# WiFi_Block_Controller_v3.net
KiCad netlist of a schematic drawn in EAGLE
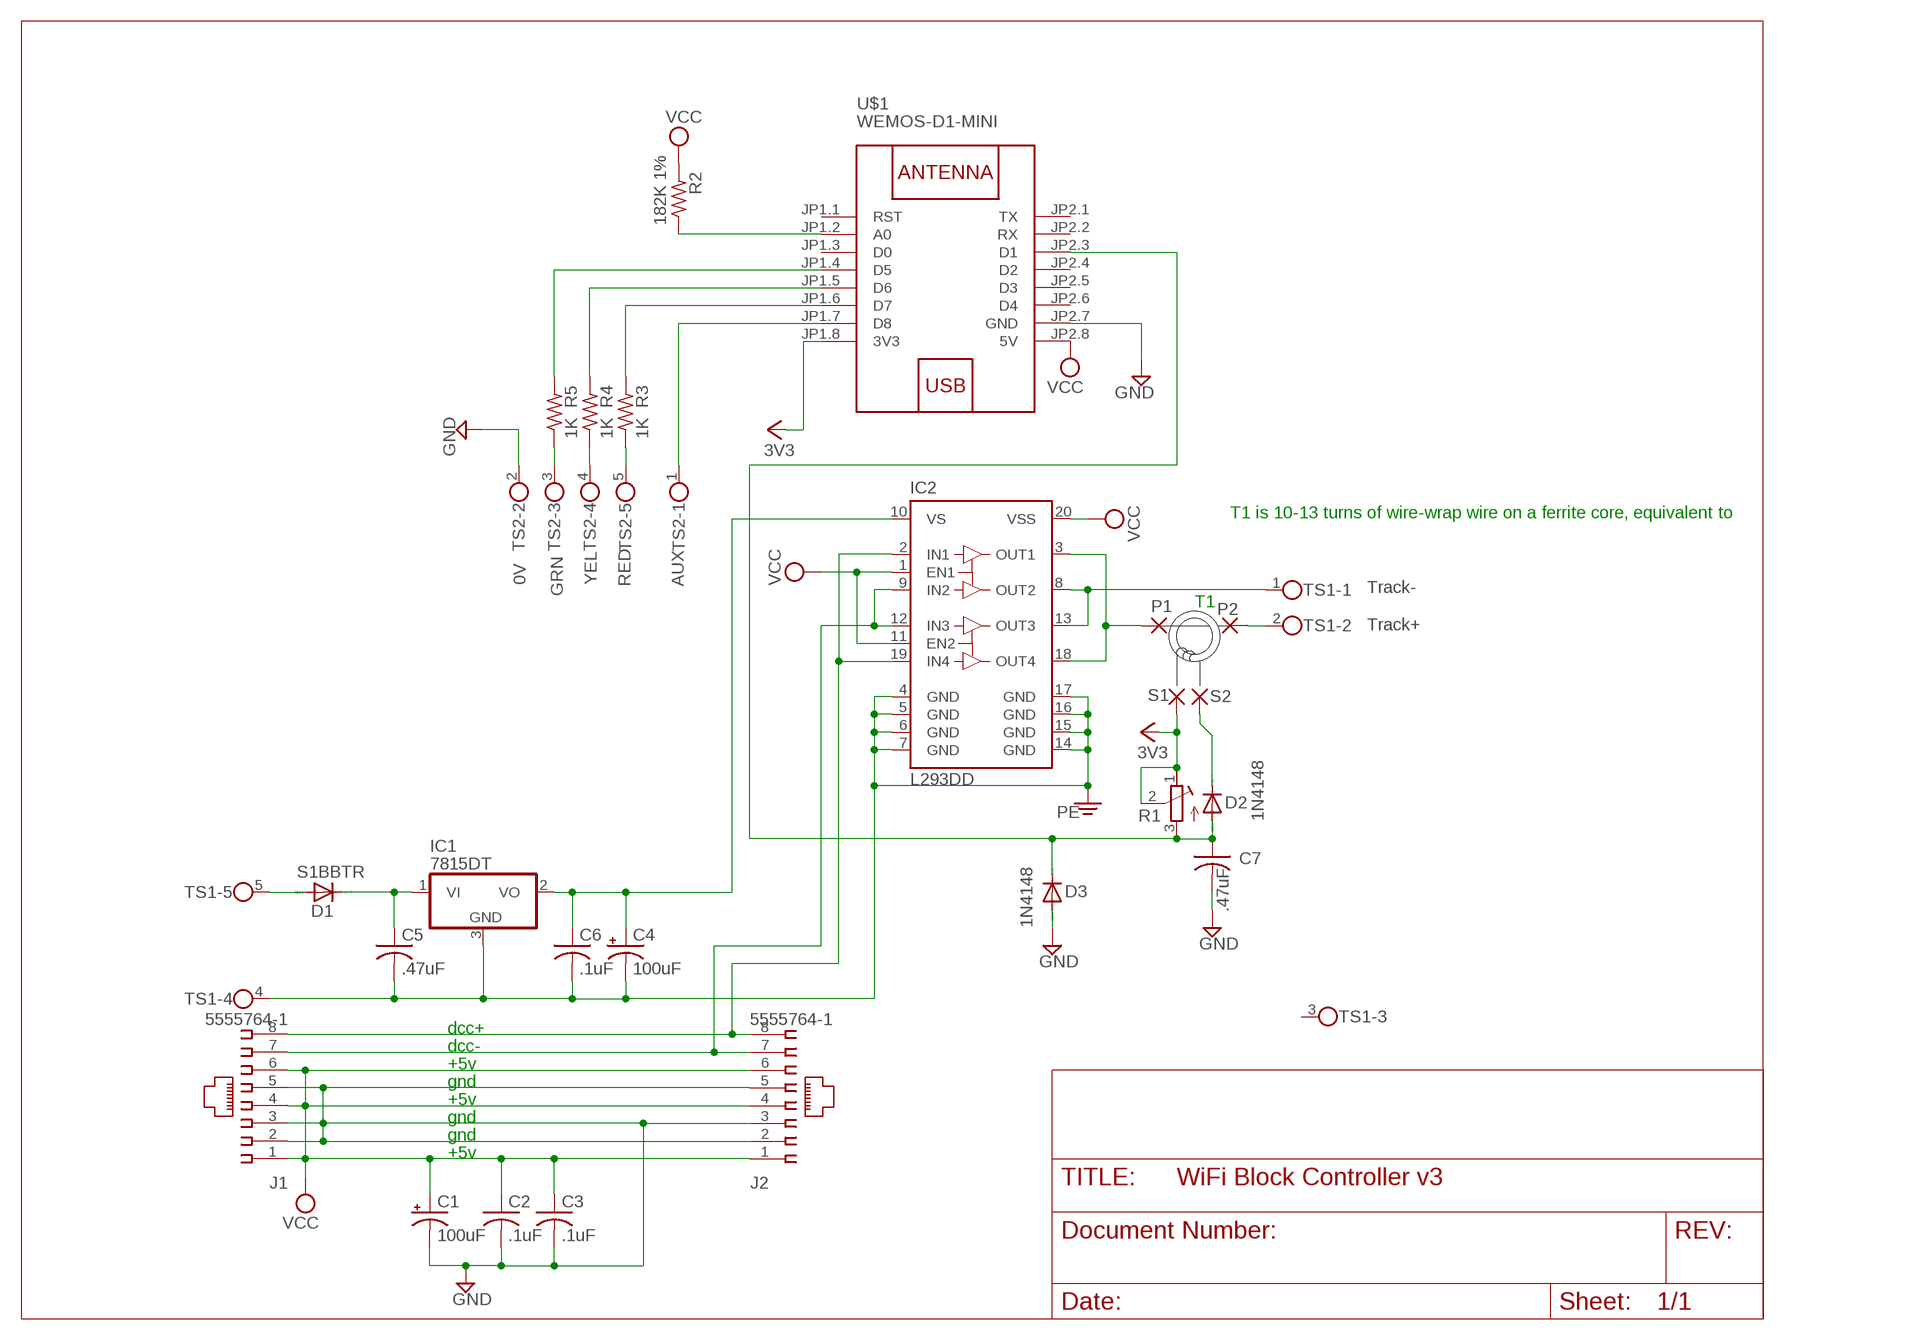
[diagram p0: schematic, sheet 1]

(export (version "E")
  (design (tool "Eeschema 10.0.6"))
  (components
    (comp (ref "C1")
      (value "100uF")
      (footprint "eagle-import:E3,5-8")
      (libsource (lib "eagle-import") (part "CPOL-USE3.5-8"))
    )
    (comp (ref "C2")
      (value ".1uF")
      (footprint "eagle-import:C1206")
      (libsource (lib "eagle-import") (part "C-USC1206"))
    )
    (comp (ref "C3")
      (value ".1uF")
      (footprint "eagle-import:C1206")
      (libsource (lib "eagle-import") (part "C-USC1206"))
    )
    (comp (ref "C4")
      (value "100uF")
      (footprint "eagle-import:E3,5-8")
      (libsource (lib "eagle-import") (part "CPOL-USE3.5-8"))
    )
    (comp (ref "C5")
      (value ".47uF")
      (footprint "eagle-import:C1206")
      (libsource (lib "eagle-import") (part "C-USC1206"))
    )
    (comp (ref "C6")
      (value ".1uF")
      (footprint "eagle-import:C1206")
      (libsource (lib "eagle-import") (part "C-USC1206"))
    )
    (comp (ref "C7")
      (value ".47uF")
      (footprint "eagle-import:C1206")
      (libsource (lib "eagle-import") (part "C-USC1206"))
    )
    (comp (ref "D1")
      (value "S1BBTR")
      (footprint "eagle-import:DO-214AC")
      (libsource (lib "eagle-import") (part "DIODE-DO-214AC"))
    )
    (comp (ref "D2")
      (value "1N4148")
      (footprint "eagle-import:SOD123")
      (libsource (lib "eagle-import") (part "DIODE-SOD123"))
    )
    (comp (ref "D3")
      (value "1N4148")
      (footprint "eagle-import:SOD123")
      (libsource (lib "eagle-import") (part "DIODE-SOD123"))
    )
    (comp (ref "IC1")
      (value "7815DT")
      (footprint "eagle-import:TO252")
      (libsource (lib "eagle-import") (part "78DT18"))
    )
    (comp (ref "IC2")
      (value "L293DD")
      (footprint "eagle-import:SO20")
      (libsource (lib "eagle-import") (part "L293DD"))
    )
    (comp (ref "J1")
      (value "5555764-1")
      (footprint "eagle-import:520426-4")
      (libsource (lib "eagle-import") (part "520426-4"))
    )
    (comp (ref "J2")
      (value "5555764-1")
      (footprint "eagle-import:520426-4")
      (libsource (lib "eagle-import") (part "520426-4"))
    )
    (comp (ref "P1")
      (value "NA")
      (footprint "eagle-import:2,15_1,0")
      (libsource (lib "eagle-import") (part "2,15/1,0"))
    )
    (comp (ref "P2")
      (value "NA")
      (footprint "eagle-import:2,15_1,0")
      (libsource (lib "eagle-import") (part "2,15/1,0"))
    )
    (comp (ref "R1")
      (value "R-TRIMM3314G")
      (footprint "eagle-import:RTRIM3314G")
      (libsource (lib "eagle-import") (part "R-TRIMM3314G"))
    )
    (comp (ref "R2")
      (value "182K 1%")
      (footprint "eagle-import:M1206")
      (libsource (lib "eagle-import") (part "R-US_M1206"))
    )
    (comp (ref "R3")
      (value "1K")
      (footprint "eagle-import:M1206")
      (libsource (lib "eagle-import") (part "R-US_M1206"))
    )
    (comp (ref "R4")
      (value "1K")
      (footprint "eagle-import:M1206")
      (libsource (lib "eagle-import") (part "R-US_M1206"))
    )
    (comp (ref "R5")
      (value "1K")
      (footprint "eagle-import:M1206")
      (libsource (lib "eagle-import") (part "R-US_M1206"))
    )
    (comp (ref "S1")
      (value "2,15/1,0")
      (footprint "eagle-import:2,15_1,0")
      (libsource (lib "eagle-import") (part "2,15/1,0"))
    )
    (comp (ref "S2")
      (value "2,15/1,0")
      (footprint "eagle-import:2,15_1,0")
      (libsource (lib "eagle-import") (part "2,15/1,0"))
    )
    (comp (ref "TS1")
      (value "TERMBLK05")
      (footprint "eagle-import:05PB")
      (libsource (lib "eagle-import") (part "TERMBLK05"))
    )
    (comp (ref "TS2")
      (value "TERMBLK05")
      (footprint "eagle-import:05PB")
      (libsource (lib "eagle-import") (part "TERMBLK05"))
    )
    (comp (ref "U$1")
      (value "WEMOS-D1-MINI")
      (footprint "eagle-import:WEMOS-D1-MINI")
      (libsource (lib "eagle-import") (part "WEMOS-D1-MINI"))
    )
  )
  (nets
    (net (code "1") (name "3V3") (class "Default")
      (node (ref "R1") (pin "1") (pinfunction "E_1") (pintype "passive"))
      (node (ref "R1") (pin "2") (pinfunction "S_2") (pintype "passive"))
      (node (ref "S1") (pin "1") (pinfunction "P_1") (pintype "passive"))
      (node (ref "U$1") (pin "JP1.8") (pinfunction "3V3_JP1.8") (pintype "power_in"))
    )
    (net (code "2") (name "GND") (class "Default")
      (node (ref "C1") (pin "-") (pinfunction "-_-") (pintype "passive"))
      (node (ref "C2") (pin "2") (pinfunction "2_2") (pintype "passive"))
      (node (ref "C3") (pin "2") (pinfunction "2_2") (pintype "passive"))
      (node (ref "C7") (pin "2") (pinfunction "2_2") (pintype "passive"))
      (node (ref "D3") (pin "A") (pinfunction "A_A") (pintype "passive"))
      (node (ref "J1") (pin "2") (pinfunction "2_2") (pintype "passive"))
      (node (ref "J1") (pin "3") (pinfunction "3_3") (pintype "passive"))
      (node (ref "J1") (pin "5") (pinfunction "5_5") (pintype "passive"))
      (node (ref "J2") (pin "2") (pinfunction "2_2") (pintype "passive"))
      (node (ref "J2") (pin "3") (pinfunction "3_3") (pintype "passive"))
      (node (ref "J2") (pin "5") (pinfunction "5_5") (pintype "passive"))
      (node (ref "TS2") (pin "2") (pinfunction "1_2") (pintype "passive"))
      (node (ref "U$1") (pin "JP2.7") (pinfunction "GND_JP2.7") (pintype "power_in"))
    )
    (net (code "3") (name "Net-(IC1-VI)") (class "Default")
      (node (ref "C5") (pin "1") (pinfunction "1_1") (pintype "passive"))
      (node (ref "D1") (pin "C") (pinfunction "C_C") (pintype "passive"))
      (node (ref "IC1") (pin "1") (pinfunction "VI_1") (pintype "input"))
    )
    (net (code "4") (name "Net-(IC1-VO)") (class "Default")
      (node (ref "C4") (pin "+") (pinfunction "+_+") (pintype "passive"))
      (node (ref "C6") (pin "1") (pinfunction "1_1") (pintype "passive"))
      (node (ref "IC1") (pin "2") (pinfunction "VO_2") (pintype "passive"))
      (node (ref "IC2") (pin "10") (pinfunction "VS_10") (pintype "power_in"))
    )
    (net (code "5") (name "Net-(IC2-IN1)") (class "Default")
      (node (ref "IC2") (pin "19") (pinfunction "IN4_19") (pintype "input"))
      (node (ref "IC2") (pin "2") (pinfunction "IN1_2") (pintype "input"))
      (node (ref "J1") (pin "8") (pinfunction "8_8") (pintype "passive"))
      (node (ref "J2") (pin "8") (pinfunction "8_8") (pintype "passive"))
    )
    (net (code "6") (name "Net-(IC2-IN2)") (class "Default")
      (node (ref "IC2") (pin "12") (pinfunction "IN3_12") (pintype "input"))
      (node (ref "IC2") (pin "9") (pinfunction "IN2_9") (pintype "input"))
      (node (ref "J1") (pin "7") (pinfunction "7_7") (pintype "passive"))
      (node (ref "J2") (pin "7") (pinfunction "7_7") (pintype "passive"))
    )
    (net (code "7") (name "Net-(IC2-OUT1)") (class "Default")
      (node (ref "IC2") (pin "18") (pinfunction "OUT4_18") (pintype "output"))
      (node (ref "IC2") (pin "3") (pinfunction "OUT1_3") (pintype "output"))
      (node (ref "P1") (pin "1") (pinfunction "P_1") (pintype "passive"))
    )
    (net (code "8") (name "Net-(IC2-OUT2)") (class "Default")
      (node (ref "IC2") (pin "13") (pinfunction "OUT3_13") (pintype "output"))
      (node (ref "IC2") (pin "8") (pinfunction "OUT2_8") (pintype "output"))
      (node (ref "TS1") (pin "1") (pinfunction "1_1") (pintype "passive"))
    )
    (net (code "9") (name "Net-(P2-P)") (class "Default")
      (node (ref "P2") (pin "1") (pinfunction "P_1") (pintype "passive"))
      (node (ref "TS1") (pin "2") (pinfunction "1_2") (pintype "passive"))
    )
    (net (code "10") (name "Net-(R1-A)") (class "Default")
      (node (ref "C7") (pin "1") (pinfunction "1_1") (pintype "passive"))
      (node (ref "D2") (pin "A") (pinfunction "A_A") (pintype "passive"))
      (node (ref "D3") (pin "C") (pinfunction "C_C") (pintype "passive"))
      (node (ref "R1") (pin "3") (pinfunction "A_3") (pintype "passive"))
      (node (ref "U$1") (pin "JP2.3") (pinfunction "D1_JP2.3") (pintype "bidirectional"))
    )
    (net (code "11") (name "Net-(S2-P)") (class "Default")
      (node (ref "D2") (pin "C") (pinfunction "C_C") (pintype "passive"))
      (node (ref "S2") (pin "1") (pinfunction "P_1") (pintype "passive"))
    )
    (net (code "12") (name "Net-(TS1E-1)") (class "Default")
      (node (ref "D1") (pin "A") (pinfunction "A_A") (pintype "passive"))
      (node (ref "TS1") (pin "5") (pinfunction "1_5") (pintype "passive"))
    )
    (net (code "13") (name "Net-(TS2C-1)") (class "Default")
      (node (ref "R5") (pin "1") (pinfunction "1_1") (pintype "passive"))
      (node (ref "TS2") (pin "3") (pinfunction "1_3") (pintype "passive"))
    )
    (net (code "14") (name "Net-(TS2D-1)") (class "Default")
      (node (ref "R4") (pin "1") (pinfunction "1_1") (pintype "passive"))
      (node (ref "TS2") (pin "4") (pinfunction "1_4") (pintype "passive"))
    )
    (net (code "15") (name "Net-(TS2E-1)") (class "Default")
      (node (ref "R3") (pin "1") (pinfunction "1_1") (pintype "passive"))
      (node (ref "TS2") (pin "5") (pinfunction "1_5") (pintype "passive"))
    )
    (net (code "16") (name "Net-(U$1-A0)") (class "Default")
      (node (ref "R2") (pin "1") (pinfunction "1_1") (pintype "passive"))
      (node (ref "U$1") (pin "JP1.2") (pinfunction "A0_JP1.2") (pintype "bidirectional"))
    )
    (net (code "17") (name "Net-(U$1-D5)") (class "Default")
      (node (ref "R5") (pin "2") (pinfunction "2_2") (pintype "passive"))
      (node (ref "U$1") (pin "JP1.4") (pinfunction "D5_JP1.4") (pintype "bidirectional"))
    )
    (net (code "18") (name "Net-(U$1-D6)") (class "Default")
      (node (ref "R4") (pin "2") (pinfunction "2_2") (pintype "passive"))
      (node (ref "U$1") (pin "JP1.5") (pinfunction "D6_JP1.5") (pintype "bidirectional"))
    )
    (net (code "19") (name "Net-(U$1-D7)") (class "Default")
      (node (ref "R3") (pin "2") (pinfunction "2_2") (pintype "passive"))
      (node (ref "U$1") (pin "JP1.6") (pinfunction "D7_JP1.6") (pintype "bidirectional"))
    )
    (net (code "20") (name "Net-(U$1-D8)") (class "Default")
      (node (ref "TS2") (pin "1") (pinfunction "1_1") (pintype "passive"))
      (node (ref "U$1") (pin "JP1.7") (pinfunction "D8_JP1.7") (pintype "bidirectional"))
    )
    (net (code "21") (name "PE") (class "Default")
      (node (ref "C4") (pin "-") (pinfunction "-_-") (pintype "passive"))
      (node (ref "C5") (pin "2") (pinfunction "2_2") (pintype "passive"))
      (node (ref "C6") (pin "2") (pinfunction "2_2") (pintype "passive"))
      (node (ref "IC1") (pin "3") (pinfunction "GND_3") (pintype "passive"))
      (node (ref "IC2") (pin "14") (pinfunction "GND_14") (pintype "power_in"))
      (node (ref "IC2") (pin "15") (pinfunction "GND_15") (pintype "power_in"))
      (node (ref "IC2") (pin "16") (pinfunction "GND_16") (pintype "power_in"))
      (node (ref "IC2") (pin "17") (pinfunction "GND_17") (pintype "power_in"))
      (node (ref "IC2") (pin "4") (pinfunction "GND_4") (pintype "power_in"))
      (node (ref "IC2") (pin "5") (pinfunction "GND_5") (pintype "power_in"))
      (node (ref "IC2") (pin "6") (pinfunction "GND_6") (pintype "power_in"))
      (node (ref "IC2") (pin "7") (pinfunction "GND_7") (pintype "power_in"))
      (node (ref "TS1") (pin "4") (pinfunction "1_4") (pintype "passive"))
    )
    (net (code "22") (name "VCC") (class "Default")
      (node (ref "C1") (pin "+") (pinfunction "+_+") (pintype "passive"))
      (node (ref "C2") (pin "1") (pinfunction "1_1") (pintype "passive"))
      (node (ref "C3") (pin "1") (pinfunction "1_1") (pintype "passive"))
      (node (ref "IC2") (pin "1") (pinfunction "EN1_1") (pintype "input"))
      (node (ref "IC2") (pin "11") (pinfunction "EN2_11") (pintype "input"))
      (node (ref "IC2") (pin "20") (pinfunction "VSS_20") (pintype "power_in"))
      (node (ref "J1") (pin "1") (pinfunction "1_1") (pintype "passive"))
      (node (ref "J1") (pin "4") (pinfunction "4_4") (pintype "passive"))
      (node (ref "J1") (pin "6") (pinfunction "6_6") (pintype "passive"))
      (node (ref "J2") (pin "1") (pinfunction "1_1") (pintype "passive"))
      (node (ref "J2") (pin "4") (pinfunction "4_4") (pintype "passive"))
      (node (ref "J2") (pin "6") (pinfunction "6_6") (pintype "passive"))
      (node (ref "R2") (pin "2") (pinfunction "2_2") (pintype "passive"))
      (node (ref "U$1") (pin "JP2.8") (pinfunction "5V_JP2.8") (pintype "power_in"))
    )
    (net (code "23") (name "unconnected-(TS1C-1-Pad3)") (class "Default")
      (node (ref "TS1") (pin "3") (pinfunction "1_3") (pintype "passive"))
    )
    (net (code "24") (name "unconnected-(U$1-D0-PadJP1.3)") (class "Default")
      (node (ref "U$1") (pin "JP1.3") (pinfunction "D0_JP1.3") (pintype "bidirectional"))
    )
    (net (code "25") (name "unconnected-(U$1-D2-PadJP2.4)") (class "Default")
      (node (ref "U$1") (pin "JP2.4") (pinfunction "D2_JP2.4") (pintype "bidirectional"))
    )
    (net (code "26") (name "unconnected-(U$1-D3-PadJP2.5)") (class "Default")
      (node (ref "U$1") (pin "JP2.5") (pinfunction "D3_JP2.5") (pintype "bidirectional"))
    )
    (net (code "27") (name "unconnected-(U$1-D4-PadJP2.6)") (class "Default")
      (node (ref "U$1") (pin "JP2.6") (pinfunction "D4_JP2.6") (pintype "bidirectional"))
    )
    (net (code "28") (name "unconnected-(U$1-RST-PadJP1.1)") (class "Default")
      (node (ref "U$1") (pin "JP1.1") (pinfunction "RST_JP1.1") (pintype "bidirectional"))
    )
    (net (code "29") (name "unconnected-(U$1-RX-PadJP2.2)") (class "Default")
      (node (ref "U$1") (pin "JP2.2") (pinfunction "RX_JP2.2") (pintype "bidirectional"))
    )
    (net (code "30") (name "unconnected-(U$1-TX-PadJP2.1)") (class "Default")
      (node (ref "U$1") (pin "JP2.1") (pinfunction "TX_JP2.1") (pintype "bidirectional"))
    )
  )
)
